# power_supply.net
KiCad netlist of a schematic drawn in Altium Designer
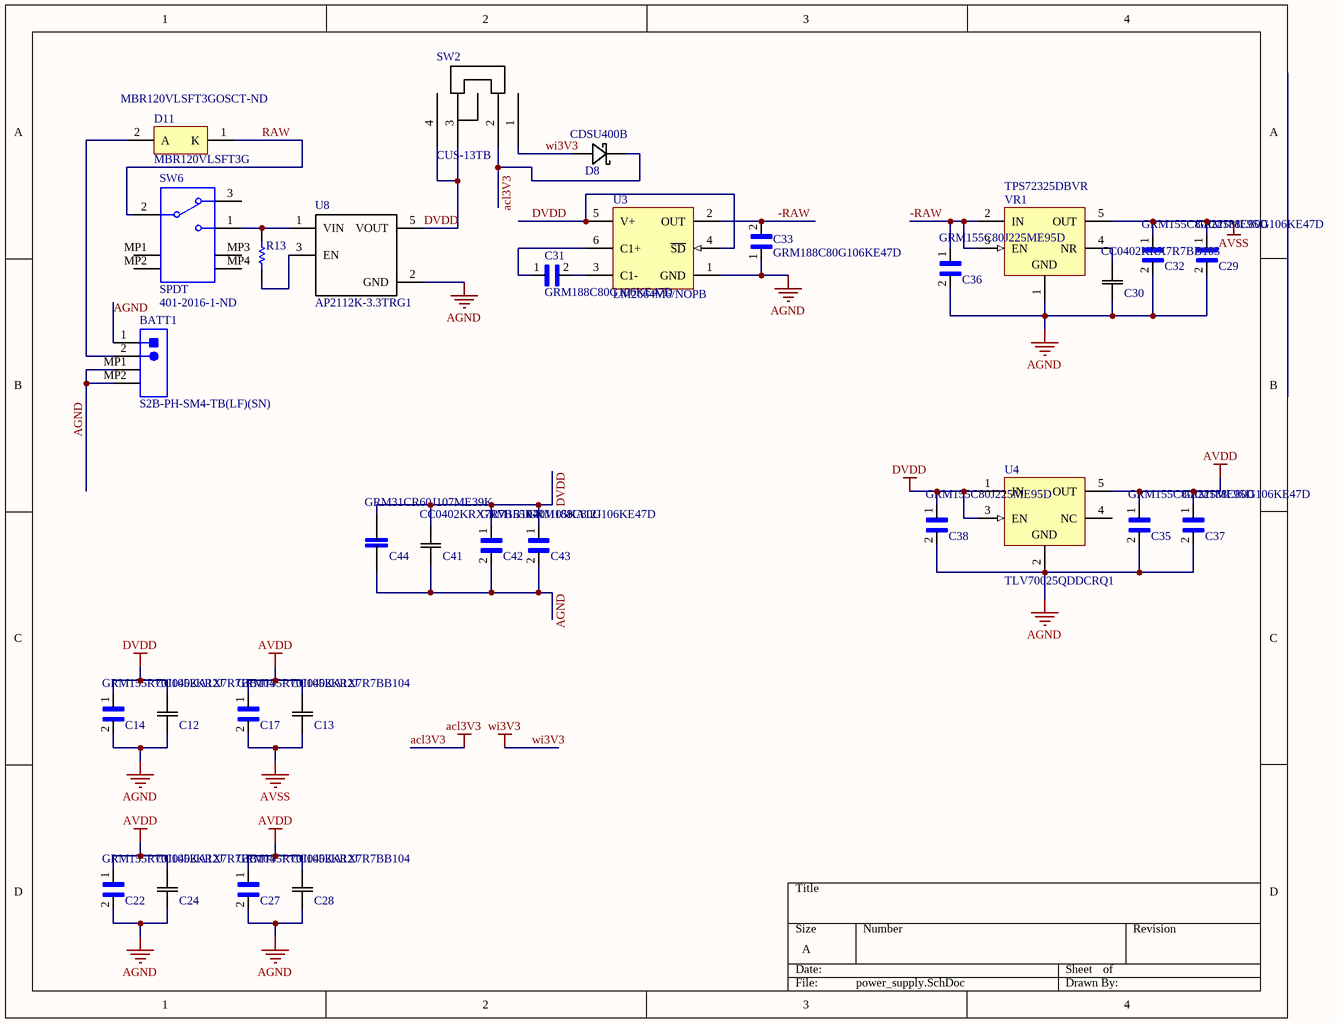
[diagram p0: power_supply.SchDoc]

(export (version "E")
  (design (tool "Eeschema 10.0.6"))
  (components
    (comp (ref "BATT1")
      (value "S2B-PH-SM4-TB(LF)(SN)")
      (footprint "JST- S2B-PH-SM4-TB(LF)(SN)-2_V")
      (libsource (lib "EE_smallOB_BW_v1.0") (part "S2B-PH-SM4-TB(LF)(SN)"))
    )
    (comp (ref "C12")
      (value "CC0402KRX7R7BB104")
      (footprint "YAG_CC0402")
      (description "CAP CER 0.1UF 16V X7R 0402")
      (fields (field (name "TOLERANCE") "10%") (field (name "VOLTAGE") "16V"))
      (libsource (lib "EE_smallOB_BW_v1.0") (part "CC0402KRX7R7BB104"))
    )
    (comp (ref "C13")
      (value "CC0402KRX7R7BB104")
      (footprint "YAG_CC0402")
      (description "CAP CER 0.1UF 16V X7R 0402")
      (fields (field (name "TOLERANCE") "10%") (field (name "VOLTAGE") "16V"))
      (libsource (lib "EE_smallOB_BW_v1.0") (part "CC0402KRX7R7BB104"))
    )
    (comp (ref "C14")
      (value "GRM155R70J105KA12J")
      (footprint "*CAPC1005X55N")
      (description "CAP CER 1UF 6.3V X7R 0402")
      (fields (field (name "TOLERANCE") "10%"))
      (libsource (lib "EE_smallOB_BW_v1.0") (part "GRM155R70J105KA12J"))
    )
    (comp (ref "C17")
      (value "GRM155R70J105KA12J")
      (footprint "*CAPC1005X55N")
      (description "CAP CER 1UF 6.3V X7R 0402")
      (fields (field (name "TOLERANCE") "10%"))
      (libsource (lib "EE_smallOB_BW_v1.0") (part "GRM155R70J105KA12J"))
    )
    (comp (ref "C22")
      (value "GRM155R70J105KA12J")
      (footprint "*CAPC1005X55N")
      (description "CAP CER 1UF 6.3V X7R 0402")
      (fields (field (name "TOLERANCE") "10%"))
      (libsource (lib "EE_smallOB_BW_v1.0") (part "GRM155R70J105KA12J"))
    )
    (comp (ref "C24")
      (value "CC0402KRX7R7BB104")
      (footprint "YAG_CC0402")
      (description "CAP CER 0.1UF 16V X7R 0402")
      (fields (field (name "TOLERANCE") "10%") (field (name "VOLTAGE") "16V"))
      (libsource (lib "EE_smallOB_BW_v1.0") (part "CC0402KRX7R7BB104"))
    )
    (comp (ref "C27")
      (value "GRM155R70J105KA12J")
      (footprint "*CAPC1005X55N")
      (description "CAP CER 1UF 6.3V X7R 0402")
      (fields (field (name "TOLERANCE") "10%"))
      (libsource (lib "EE_smallOB_BW_v1.0") (part "GRM155R70J105KA12J"))
    )
    (comp (ref "C28")
      (value "CC0402KRX7R7BB104")
      (footprint "YAG_CC0402")
      (description "CAP CER 0.1UF 16V X7R 0402")
      (fields (field (name "TOLERANCE") "10%") (field (name "VOLTAGE") "16V"))
      (libsource (lib "EE_smallOB_BW_v1.0") (part "CC0402KRX7R7BB104"))
    )
    (comp (ref "C29")
      (value "GRM188C80G106KE47D")
      (footprint "*CAPC1608X90N")
      (description "CAP CER 10UF 4V X6S 0603")
      (fields (field (name "TOLERANCE") "10%"))
      (libsource (lib "EE_smallOB_BW_v1.0") (part "GRM188C80G106KE47D"))
    )
    (comp (ref "C30")
      (value "CC0402KRX7R7BB103")
      (footprint "CC0402N")
      (description "CAP CER 10000PF 16V X7R 0402")
      (fields (field (name "TOLERANCE") "10%") (field (name "VOLTAGE") "16V"))
      (libsource (lib "EE_smallOB_BW_v1.0") (part "CC0402KRX7R7BB103"))
    )
    (comp (ref "C31")
      (value "GRM188C80G106KE47D")
      (footprint "*CAPC1608X90N")
      (description "CAP CER 10UF 4V X6S 0603")
      (fields (field (name "TOLERANCE") "10%"))
      (libsource (lib "EE_smallOB_BW_v1.0") (part "GRM188C80G106KE47D"))
    )
    (comp (ref "C32")
      (value "GRM155C80J225ME95D")
      (footprint "*CAPC1005X55N")
      (description "0402 6.3 V 2.2 uF ±20% Tolerance X6S Monolithic Ceramic Chip Capacitor")
      (fields (field (name "TOLERANCE") "20%"))
      (libsource (lib "EE_smallOB_BW_v1.0") (part "GRM155C80J225ME95D"))
    )
    (comp (ref "C33")
      (value "GRM188C80G106KE47D")
      (footprint "*CAPC1608X90N")
      (description "CAP CER 10UF 4V X6S 0603")
      (fields (field (name "TOLERANCE") "10%"))
      (libsource (lib "EE_smallOB_BW_v1.0") (part "GRM188C80G106KE47D"))
    )
    (comp (ref "C35")
      (value "GRM155C80J225ME95D")
      (footprint "*CAPC1005X55N")
      (description "0402 6.3 V 2.2 uF ±20% Tolerance X6S Monolithic Ceramic Chip Capacitor")
      (fields (field (name "TOLERANCE") "20%"))
      (libsource (lib "EE_smallOB_BW_v1.0") (part "GRM155C80J225ME95D"))
    )
    (comp (ref "C36")
      (value "GRM155C80J225ME95D")
      (footprint "*CAPC1005X55N")
      (description "0402 6.3 V 2.2 uF ±20% Tolerance X6S Monolithic Ceramic Chip Capacitor")
      (fields (field (name "TOLERANCE") "20%"))
      (libsource (lib "EE_smallOB_BW_v1.0") (part "GRM155C80J225ME95D"))
    )
    (comp (ref "C37")
      (value "GRM188C80G106KE47D")
      (footprint "*CAPC1608X90N")
      (description "CAP CER 10UF 4V X6S 0603")
      (fields (field (name "TOLERANCE") "10%"))
      (libsource (lib "EE_smallOB_BW_v1.0") (part "GRM188C80G106KE47D"))
    )
    (comp (ref "C38")
      (value "GRM155C80J225ME95D")
      (footprint "*CAPC1005X55N")
      (description "0402 6.3 V 2.2 uF ±20% Tolerance X6S Monolithic Ceramic Chip Capacitor")
      (fields (field (name "TOLERANCE") "20%"))
      (libsource (lib "EE_smallOB_BW_v1.0") (part "GRM155C80J225ME95D"))
    )
    (comp (ref "C41")
      (value "CC0402KRX7R7BB104")
      (footprint "YAG_CC0402")
      (description "CAP CER 0.1UF 16V X7R 0402")
      (fields (field (name "TOLERANCE") "10%") (field (name "VOLTAGE") "16V"))
      (libsource (lib "EE_smallOB_BW_v1.0") (part "CC0402KRX7R7BB104"))
    )
    (comp (ref "C42")
      (value "GRM155R70J105KA12J")
      (footprint "*CAPC1005X55N")
      (description "CAP CER 1UF 6.3V X7R 0402")
      (fields (field (name "TOLERANCE") "10%"))
      (libsource (lib "EE_smallOB_BW_v1.0") (part "GRM155R70J105KA12J"))
    )
    (comp (ref "C43")
      (value "GRM188C80G106KE47D")
      (footprint "*CAPC1608X90N")
      (description "CAP CER 10UF 4V X6S 0603")
      (fields (field (name "TOLERANCE") "10%"))
      (libsource (lib "EE_smallOB_BW_v1.0") (part "GRM188C80G106KE47D"))
    )
    (comp (ref "C44")
      (value "GRM31CR60J107ME39K")
      (footprint "*CAPC3216X190")
      (description "MURATA - GRM31CR60J107ME39K - COND, 100µF, 6.3V, 20%, X5R, 1206")
      (fields (field (name "TOLERANCE") "20%") (field (name "VOLTAGE") "6.3V"))
      (libsource (lib "EE_smallOB_BW_v1.0") (part "GRM31CR60J107ME39K"))
    )
    (comp (ref "D8")
      (value "CDSU400B")
      (footprint "EE_smallOB_BW_v1.0:CDBU")
      (description "DIODE GEN PURP 80V 100MA 0603")
      (libsource (lib "EE_smallOB_BW_v1.0") (part "CDSU400B"))
    )
    (comp (ref "D11")
      (value "MBR120VLSFT3G")
      (footprint "ONSC-SOD-123FL-2-498-01_V")
      (description "MBR120VLSF Series 20 V 1 A Surface Mount Schottky Power Rectifier - SOD-123FL")
      (fields (field (name "SUPPLIER PART NUMBER 1") "MBR120VLSFT3GOSCT-ND"))
      (libsource (lib "EE_smallOB_BW_v1.0") (part "MBR120VLSFT3G"))
    )
    (comp (ref "R13")
      (value "10K")
      (footprint "RESC1609X55X30NL15T15")
      (description "Res Thick Film 0603 10K Ohm 1% 1/10W ±100ppm/°C Molded SMD Punched Carrier T/R")
      (fields (field (name "TOLERANCE") "1%"))
      (libsource (lib "EE_smallOB_BW_v1.0") (part "ERJ-3EKF1002V"))
    )
    (comp (ref "SW2")
      (value "CUS-13TB")
      (footprint "CUS-13TB")
      (description "SWITCH SLIDE SP3T 300MA 4V")
      (libsource (lib "EE_smallOB_BW_v1.0") (part "CUS-13TB"))
    )
    (comp (ref "SW6")
      (value "SPDT")
      (footprint "CKCP-PCM12SMTR_V")
      (description "C & K COMPONENTS - PCM12SMTR - SWITCH, SPDT, 0.3A, 6VDC, SMD")
      (fields (field (name "SUPPLIER PART NUMBER 1") "401-2016-1-ND"))
      (libsource (lib "EE_smallOB_BW_v1.0") (part "PCM12SMTR"))
    )
    (comp (ref "U3")
      (value "LM2664M6/NOPB")
      (footprint "DBV0006A_N")
      (description "IC REG SWTCHD CAP INV 40MA SOT23")
      (libsource (lib "EE_smallOB_BW_v1.0") (part "LM2664M6/NOPB"))
    )
    (comp (ref "U4")
      (value "TLV70025QDDCRQ1")
      (footprint "DDC0005A_N")
      (description "LDO Regulator Pos 2.5V 0.2A 5-Pin SOT T/R")
      (libsource (lib "EE_smallOB_BW_v1.0") (part "TLV70025QDDCRQ1"))
    )
    (comp (ref "U8")
      (value "AP2112K-3.3TRG1")
      (footprint "*SOT95P285X140-5N")
      (description "IC REG LINEAR 3.3V 600MA SOT25")
      (libsource (lib "EE_smallOB_BW_v1.0") (part "AP2112K-3.3TRG1"))
    )
    (comp (ref "VR1")
      (value "TPS72325DBVR")
      (footprint "DBV0005A_N")
      (description "200 mA Low-Noise, High-PSRR Negative Output Low-Dropout Linear Regulators")
      (libsource (lib "EE_smallOB_BW_v1.0") (part "TPS72325DBVR"))
    )
  )
  (nets
    (net (code "1") (name "/-RAW") (class "Default")
      (node (ref "C33") (pin "2") (pinfunction "2_2") (pintype "passive"))
      (node (ref "C36") (pin "1") (pinfunction "1_1") (pintype "passive"))
      (node (ref "U3") (pin "2") (pinfunction "OUT_2") (pintype "power_in"))
      (node (ref "VR1") (pin "2") (pinfunction "IN_2") (pintype "power_in"))
      (node (ref "VR1") (pin "3") (pinfunction "EN_3") (pintype "input"))
    )
    (net (code "2") (name "/RAW") (class "Default")
      (node (ref "D11") (pin "1") (pinfunction "K_1") (pintype "passive"))
      (node (ref "SW6") (pin "2") (pinfunction "2_2") (pintype "passive"))
    )
    (net (code "3") (name "AGND") (class "Default")
      (node (ref "BATT1") (pin "1") (pinfunction "1_1") (pintype "passive"))
      (node (ref "BATT1") (pin "MP1") (pinfunction "MP1_MP1") (pintype "passive"))
      (node (ref "BATT1") (pin "MP2") (pinfunction "MP2_MP2") (pintype "passive"))
      (node (ref "C12") (pin "2") (pinfunction "2_2") (pintype "passive"))
      (node (ref "C14") (pin "2") (pinfunction "2_2") (pintype "passive"))
      (node (ref "C22") (pin "2") (pinfunction "2_2") (pintype "passive"))
      (node (ref "C24") (pin "2") (pinfunction "2_2") (pintype "passive"))
      (node (ref "C27") (pin "2") (pinfunction "2_2") (pintype "passive"))
      (node (ref "C28") (pin "2") (pinfunction "2_2") (pintype "passive"))
      (node (ref "C29") (pin "2") (pinfunction "2_2") (pintype "passive"))
      (node (ref "C30") (pin "1") (pinfunction "1_1") (pintype "passive"))
      (node (ref "C32") (pin "2") (pinfunction "2_2") (pintype "passive"))
      (node (ref "C33") (pin "1") (pinfunction "1_1") (pintype "passive"))
      (node (ref "C35") (pin "2") (pinfunction "2_2") (pintype "passive"))
      (node (ref "C36") (pin "2") (pinfunction "2_2") (pintype "passive"))
      (node (ref "C37") (pin "2") (pinfunction "2_2") (pintype "passive"))
      (node (ref "C38") (pin "2") (pinfunction "2_2") (pintype "passive"))
      (node (ref "C41") (pin "2") (pinfunction "2_2") (pintype "passive"))
      (node (ref "C42") (pin "2") (pinfunction "2_2") (pintype "passive"))
      (node (ref "C43") (pin "2") (pinfunction "2_2") (pintype "passive"))
      (node (ref "C44") (pin "2") (pinfunction "2_2") (pintype "passive"))
      (node (ref "U3") (pin "1") (pinfunction "GND_1") (pintype "power_in"))
      (node (ref "U4") (pin "2") (pinfunction "GND_2") (pintype "power_in"))
      (node (ref "U8") (pin "2") (pinfunction "GND_2") (pintype "power_in"))
      (node (ref "VR1") (pin "1") (pinfunction "GND_1") (pintype "power_in"))
    )
    (net (code "4") (name "AVDD") (class "Default")
      (node (ref "C13") (pin "1") (pinfunction "1_1") (pintype "passive"))
      (node (ref "C17") (pin "1") (pinfunction "1_1") (pintype "passive"))
      (node (ref "C22") (pin "1") (pinfunction "1_1") (pintype "passive"))
      (node (ref "C24") (pin "1") (pinfunction "1_1") (pintype "passive"))
      (node (ref "C27") (pin "1") (pinfunction "1_1") (pintype "passive"))
      (node (ref "C28") (pin "1") (pinfunction "1_1") (pintype "passive"))
      (node (ref "C35") (pin "1") (pinfunction "1_1") (pintype "passive"))
      (node (ref "C37") (pin "1") (pinfunction "1_1") (pintype "passive"))
      (node (ref "U4") (pin "5") (pinfunction "OUT_5") (pintype "power_in"))
    )
    (net (code "5") (name "AVSS") (class "Default")
      (node (ref "C13") (pin "2") (pinfunction "2_2") (pintype "passive"))
      (node (ref "C17") (pin "2") (pinfunction "2_2") (pintype "passive"))
      (node (ref "C29") (pin "1") (pinfunction "1_1") (pintype "passive"))
      (node (ref "C32") (pin "1") (pinfunction "1_1") (pintype "passive"))
      (node (ref "VR1") (pin "5") (pinfunction "OUT_5") (pintype "power_in"))
    )
    (net (code "6") (name "DVDD") (class "Default")
      (node (ref "C12") (pin "1") (pinfunction "1_1") (pintype "passive"))
      (node (ref "C14") (pin "1") (pinfunction "1_1") (pintype "passive"))
      (node (ref "C38") (pin "1") (pinfunction "1_1") (pintype "passive"))
      (node (ref "C41") (pin "1") (pinfunction "1_1") (pintype "passive"))
      (node (ref "C42") (pin "1") (pinfunction "1_1") (pintype "passive"))
      (node (ref "C43") (pin "1") (pinfunction "1_1") (pintype "passive"))
      (node (ref "C44") (pin "1") (pinfunction "1_1") (pintype "passive"))
      (node (ref "SW2") (pin "3") (pinfunction "3_3") (pintype "passive"))
      (node (ref "SW2") (pin "4") (pinfunction "4_4") (pintype "passive"))
      (node (ref "U3") (pin "4") (pinfunction "~{SD}_4") (pintype "input"))
      (node (ref "U3") (pin "5") (pinfunction "V+_5") (pintype "power_in"))
      (node (ref "U4") (pin "1") (pinfunction "IN_1") (pintype "power_in"))
      (node (ref "U4") (pin "3") (pinfunction "EN_3") (pintype "input"))
      (node (ref "U8") (pin "5") (pinfunction "VOUT_5") (pintype "power_in"))
    )
    (net (code "7") (name "Net-(D11-A)") (class "Default")
      (node (ref "BATT1") (pin "2") (pinfunction "2_2") (pintype "passive"))
      (node (ref "D11") (pin "2") (pinfunction "A_2") (pintype "passive"))
    )
    (net (code "8") (name "Net-(U3-C1+)") (class "Default")
      (node (ref "C31") (pin "1") (pinfunction "1_1") (pintype "passive"))
      (node (ref "U3") (pin "6") (pinfunction "C1+_6") (pintype "passive"))
    )
    (net (code "9") (name "Net-(U3-C1-)") (class "Default")
      (node (ref "C31") (pin "2") (pinfunction "2_2") (pintype "passive"))
      (node (ref "U3") (pin "3") (pinfunction "C1-_3") (pintype "passive"))
    )
    (net (code "10") (name "Net-(U8-EN)") (class "Default")
      (node (ref "R13") (pin "1") (pinfunction "1_1") (pintype "passive"))
      (node (ref "U8") (pin "3") (pinfunction "EN_3") (pintype "passive"))
    )
    (net (code "11") (name "Net-(U8-VIN)") (class "Default")
      (node (ref "R13") (pin "2") (pinfunction "2_2") (pintype "passive"))
      (node (ref "SW6") (pin "1") (pinfunction "1_1") (pintype "passive"))
      (node (ref "U8") (pin "1") (pinfunction "VIN_1") (pintype "power_in"))
    )
    (net (code "12") (name "Net-(VR1-NR)") (class "Default")
      (node (ref "C30") (pin "2") (pinfunction "2_2") (pintype "passive"))
      (node (ref "VR1") (pin "4") (pinfunction "NR_4") (pintype "passive"))
    )
    (net (code "13") (name "acl3V3") (class "Default")
      (node (ref "D8") (pin "1") (pinfunction "1_1") (pintype "passive"))
      (node (ref "SW2") (pin "2") (pinfunction "2_2") (pintype "passive"))
    )
    (net (code "14") (name "unconnected-(SW6-Pad3)") (class "Default")
      (node (ref "SW6") (pin "3") (pinfunction "3_3") (pintype "passive"))
    )
    (net (code "15") (name "unconnected-(SW6-PadMP1)") (class "Default")
      (node (ref "SW6") (pin "MP1") (pinfunction "MP1_MP1") (pintype "passive"))
    )
    (net (code "16") (name "unconnected-(SW6-PadMP2)") (class "Default")
      (node (ref "SW6") (pin "MP2") (pinfunction "MP2_MP2") (pintype "passive"))
    )
    (net (code "17") (name "unconnected-(SW6-PadMP3)") (class "Default")
      (node (ref "SW6") (pin "MP3") (pinfunction "MP3_MP3") (pintype "passive"))
    )
    (net (code "18") (name "unconnected-(SW6-PadMP4)") (class "Default")
      (node (ref "SW6") (pin "MP4") (pinfunction "MP4_MP4") (pintype "passive"))
    )
    (net (code "19") (name "unconnected-(U4-NC-Pad4)") (class "Default")
      (node (ref "U4") (pin "4") (pinfunction "NC_4") (pintype "passive"))
    )
    (net (code "20") (name "wi3V3") (class "Default")
      (node (ref "D8") (pin "2") (pinfunction "2_2") (pintype "passive"))
      (node (ref "SW2") (pin "1") (pinfunction "1_1") (pintype "passive"))
    )
  )
)
